# MOSFET_IRLML0030.net
KiCad netlist of a schematic drawn in Altium Designer
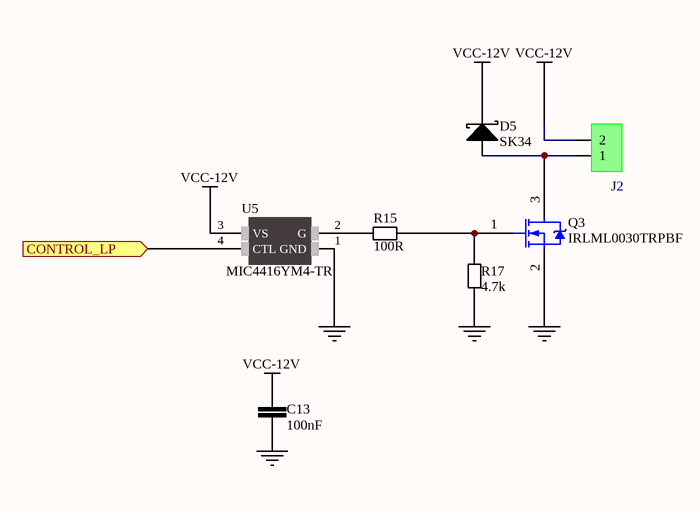
[diagram p0: MOSFET_IRLML0030.SchDoc]

(export (version "E")
  (design (tool "Eeschema 10.0.6"))
  (components
    (comp (ref "C13")
      (value "100nF")
      (footprint "CER_0805")
      (description "CAP CER 100n 50V X7R 10% 0805")
      (libsource (lib "Capacitors") (part "00002105"))
    )
    (comp (ref "D5")
      (value "SK34")
      (footprint "DO214AC")
      (description "DIODE SCHOTTKY 40V 3A DO214AC")
      (fields (field (name "MANUFACTURER") "Vishay Semiconductor Diodes Division"))
      (libsource (lib "Discrete_Semiconductor") (part "SK34"))
    )
    (comp (ref "J2")
      (value "282834-2")
      (footprint "CONNECTOR_282834-2")
      (description "Wire-To-Board Terminal Block, 2, 150 V, 10 A, 30 Awg, 16 Awg, 1.4 Mm")
      (fields (field (name "DIGI-KEY_PART_NUMBER") "A98333-ND") (field (name "MF") "TE Connectivity"))
      (libsource (lib "Electro_Mechanical") (part "TE 282834-2"))
    )
    (comp (ref "Q3")
      (value "IRLML0030TRPBF")
      (footprint "SOT-23")
      (description "N-MOS")
      (fields (field (name "MANUFACTURER") "INFINEON"))
      (libsource (lib "Discrete_Semiconductor") (part "IRLML0030"))
    )
    (comp (ref "R15")
      (value "100R")
      (footprint "RESC2013X38N-0805-NOOVERLAY")
      (description "RES SMD 100 Ohm 1/8W 0805")
      (fields (field (name "POWER") "0.125W, 1/8W"))
      (libsource (lib "Resistors") (part "00001000"))
    )
    (comp (ref "R17")
      (value "4.7k")
      (footprint "RESC2013X38N-0805-NOOVERLAY")
      (description "RES SMD 4.7 kOhm 1/8W 0805")
      (fields (field (name "POWER") "0.125W, 1/8W"))
      (libsource (lib "Resistors") (part "00004701"))
    )
    (comp (ref "U5")
      (value "MIC4416YM4-TR")
      (footprint "SOT143-4")
      (description "IC DRIVER MOSF LOW SIDE SOT143-4")
      (libsource (lib "Integrated_circuits") (part "MIC4416"))
    )
  )
  (nets
    (net (code "1") (name "/CONTROL_LP") (class "Default")
      (node (ref "U5") (pin "4") (pinfunction "CTL_4") (pintype "passive"))
    )
    (net (code "2") (name "GND") (class "Default")
      (node (ref "C13") (pin "1") (pinfunction "1_1") (pintype "passive"))
      (node (ref "Q3") (pin "2") (pinfunction "D_2") (pintype "passive"))
      (node (ref "R17") (pin "1") (pinfunction "1_1") (pintype "passive"))
      (node (ref "U5") (pin "1") (pinfunction "GND_1") (pintype "passive"))
    )
    (net (code "3") (name "Net-(D5-Anode)") (class "Default")
      (node (ref "D5") (pin "2") (pinfunction "Anode_2") (pintype "passive"))
      (node (ref "J2") (pin "1") (pinfunction "1_1") (pintype "passive"))
      (node (ref "Q3") (pin "3") (pinfunction "S_3") (pintype "passive"))
    )
    (net (code "4") (name "Net-(Q3-G)") (class "Default")
      (node (ref "Q3") (pin "1") (pinfunction "G_1") (pintype "passive"))
      (node (ref "R15") (pin "2") (pinfunction "2_2") (pintype "passive"))
      (node (ref "R17") (pin "2") (pinfunction "2_2") (pintype "passive"))
    )
    (net (code "5") (name "Net-(U5-G)") (class "Default")
      (node (ref "R15") (pin "1") (pinfunction "1_1") (pintype "passive"))
      (node (ref "U5") (pin "2") (pinfunction "G_2") (pintype "passive"))
    )
    (net (code "6") (name "VCC-12V") (class "Default")
      (node (ref "C13") (pin "2") (pinfunction "2_2") (pintype "passive"))
      (node (ref "D5") (pin "1") (pinfunction "Cathode_1") (pintype "passive"))
      (node (ref "J2") (pin "2") (pinfunction "2_2") (pintype "passive"))
      (node (ref "U5") (pin "3") (pinfunction "VS_3") (pintype "passive"))
    )
  )
)
